# sc_v0.net
KiCad netlist of a schematic drawn in EAGLE
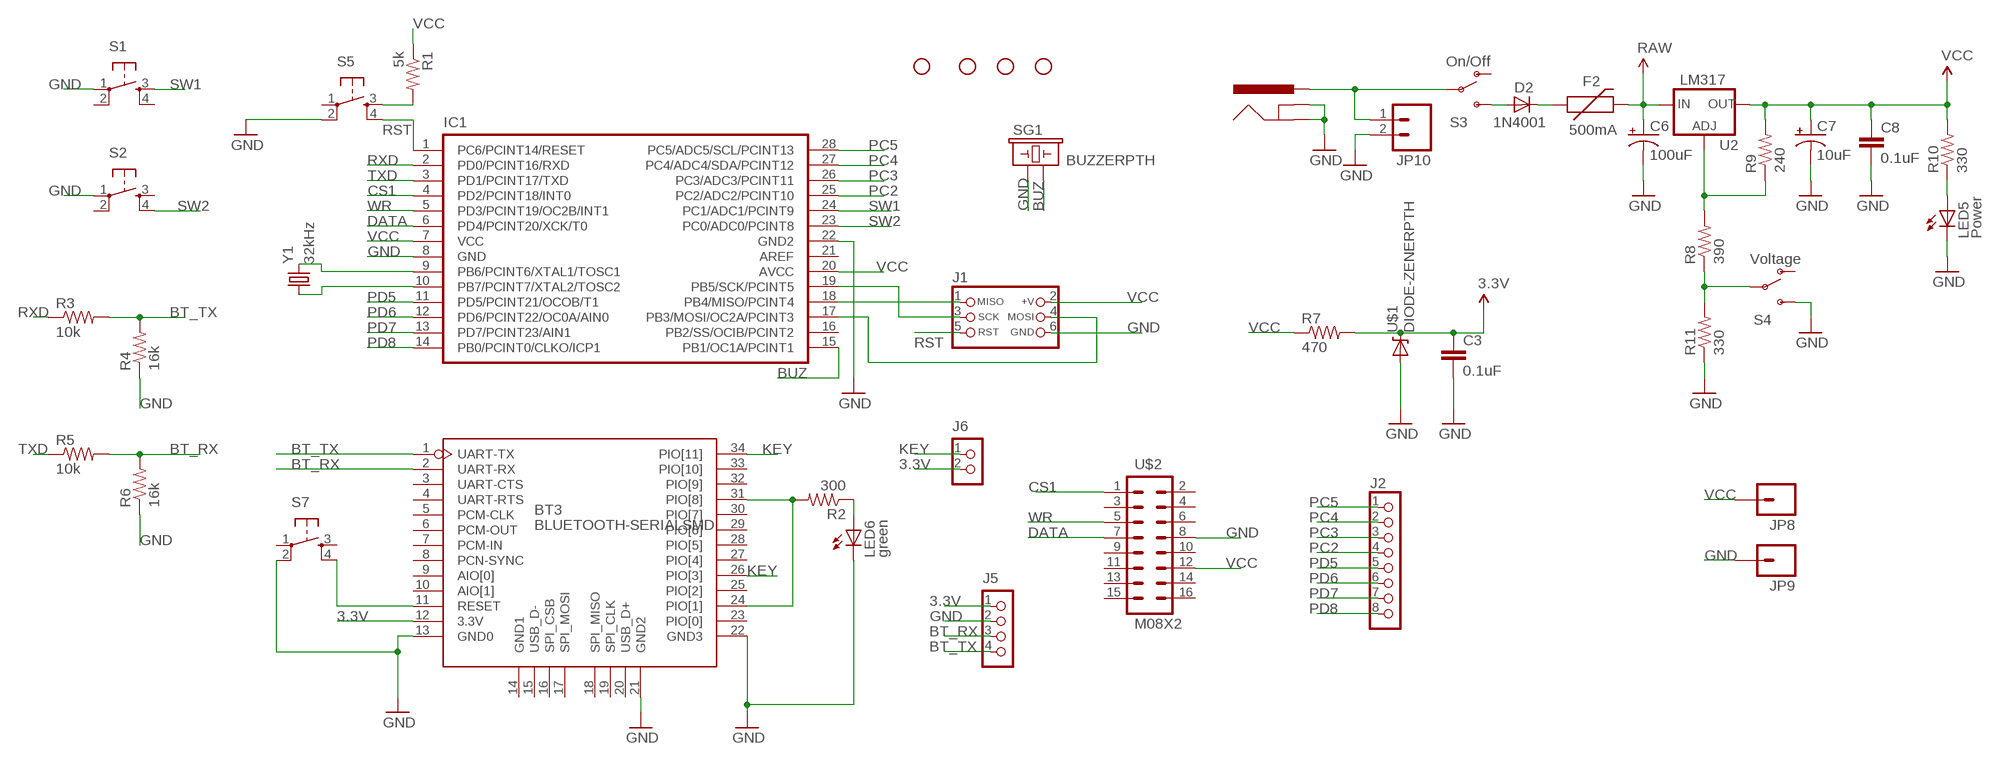
[diagram p0: schematic, sheet 1]

(export (version "E")
  (design (tool "Eeschema 10.0.6"))
  (components
    (comp (ref "BT3")
      (value "BLUETOOTH-SERIALSMD")
      (footprint "eagle-import:SERIAL_BLUETEETH")
      (libsource (lib "eagle-import") (part "BLUETOOTH-SERIALSMD"))
    )
    (comp (ref "C3")
      (value "0.1uF")
      (footprint "eagle-import:CAP-PTH-SMALL2")
      (libsource (lib "eagle-import") (part "CAPPTH2"))
    )
    (comp (ref "C6")
      (value "100uF")
      (footprint "eagle-import:CPOL-RADIAL-100UF-25V")
      (libsource (lib "eagle-import") (part "CAP_POLPTH1"))
    )
    (comp (ref "C7")
      (value "10uF")
      (footprint "eagle-import:CPOL-RADIAL-10UF-25V")
      (libsource (lib "eagle-import") (part "CAP_POLPTH2"))
    )
    (comp (ref "C8")
      (value "0.1uF")
      (footprint "eagle-import:CAP-PTH-SMALL2")
      (libsource (lib "eagle-import") (part "CAPPTH2"))
    )
    (comp (ref "D2")
      (value "1N4001")
      (footprint "eagle-import:DIODE-0.4")
      (libsource (lib "eagle-import") (part "DIODEPTH"))
    )
    (comp (ref "F2")
      (value "500mA")
      (footprint "eagle-import:PTC")
      (libsource (lib "eagle-import") (part "PTCPTH"))
    )
    (comp (ref "IC1")
      (value "IC_UC_ATMEGA328PDIL")
      (footprint "eagle-import:DIL28-N")
      (libsource (lib "eagle-import") (part "IC_UC_ATMEGA328PDIL"))
    )
    (comp (ref "J1")
      (value "CON_HEADER_PRG_AVR_ICSP")
      (footprint "eagle-import:HEADER_PRG_2X03")
      (libsource (lib "eagle-import") (part "CON_HEADER_PRG_AVR_ICSP"))
    )
    (comp (ref "J2")
      (value "CON_HEADER_1X08-PTH")
      (footprint "eagle-import:M1X8")
      (libsource (lib "eagle-import") (part "CON_HEADER_1X08-PTH"))
    )
    (comp (ref "J3")
      (value "POWER_JACKPTH")
      (footprint "eagle-import:POWER_JACK_PTH")
      (libsource (lib "eagle-import") (part "POWER_JACKPTH"))
    )
    (comp (ref "J5")
      (value "CON_HEADER_1X04")
      (footprint "eagle-import:M1X4")
      (libsource (lib "eagle-import") (part "CON_HEADER_1X04"))
    )
    (comp (ref "J6")
      (value "CON_HEADER_1X02-PTH")
      (footprint "eagle-import:M1X2")
      (libsource (lib "eagle-import") (part "CON_HEADER_1X02-PTH"))
    )
    (comp (ref "JP1")
      (value "STAND-OFF")
      (footprint "eagle-import:STAND-OFF")
      (libsource (lib "eagle-import") (part "STAND-OFF"))
    )
    (comp (ref "JP2")
      (value "STAND-OFF")
      (footprint "eagle-import:STAND-OFF")
      (libsource (lib "eagle-import") (part "STAND-OFF"))
    )
    (comp (ref "JP3")
      (value "STAND-OFF")
      (footprint "eagle-import:STAND-OFF")
      (libsource (lib "eagle-import") (part "STAND-OFF"))
    )
    (comp (ref "JP4")
      (value "STAND-OFF")
      (footprint "eagle-import:STAND-OFF")
      (libsource (lib "eagle-import") (part "STAND-OFF"))
    )
    (comp (ref "JP8")
      (value "M01PTH")
      (footprint "eagle-import:1X01")
      (libsource (lib "eagle-import") (part "M01PTH"))
    )
    (comp (ref "JP9")
      (value "M01PTH")
      (footprint "eagle-import:1X01")
      (libsource (lib "eagle-import") (part "M01PTH"))
    )
    (comp (ref "JP10")
      (value "M02PTH")
      (footprint "eagle-import:1X02")
      (libsource (lib "eagle-import") (part "M02PTH"))
    )
    (comp (ref "LED5")
      (value "Power")
      (footprint "eagle-import:LED5MM")
      (libsource (lib "eagle-import") (part "SparkFun-Nate_LED5MM"))
    )
    (comp (ref "LED6")
      (value "green")
      (footprint "eagle-import:LED3MM")
      (libsource (lib "eagle-import") (part "LED3MM"))
    )
    (comp (ref "R1")
      (value "5k")
      (footprint "eagle-import:AXIAL-0.3")
      (libsource (lib "eagle-import") (part "RESISTORAXIAL-0.3"))
    )
    (comp (ref "R2")
      (value "300")
      (footprint "eagle-import:AXIAL-0.3")
      (libsource (lib "eagle-import") (part "RESISTORAXIAL-0.3"))
    )
    (comp (ref "R3")
      (value "10k")
      (footprint "eagle-import:AXIAL-0.3")
      (libsource (lib "eagle-import") (part "RESISTORAXIAL-0.3"))
    )
    (comp (ref "R4")
      (value "16k")
      (footprint "eagle-import:AXIAL-0.3")
      (libsource (lib "eagle-import") (part "RESISTORAXIAL-0.3"))
    )
    (comp (ref "R5")
      (value "10k")
      (footprint "eagle-import:AXIAL-0.3")
      (libsource (lib "eagle-import") (part "RESISTORAXIAL-0.3"))
    )
    (comp (ref "R6")
      (value "16k")
      (footprint "eagle-import:AXIAL-0.3")
      (libsource (lib "eagle-import") (part "RESISTORAXIAL-0.3"))
    )
    (comp (ref "R7")
      (value "470")
      (footprint "eagle-import:AXIAL-0.3")
      (libsource (lib "eagle-import") (part "RESISTORAXIAL-0.3"))
    )
    (comp (ref "R8")
      (value "390")
      (footprint "eagle-import:AXIAL-0.3")
      (libsource (lib "eagle-import") (part "RESISTORAXIAL-0.3"))
    )
    (comp (ref "R9")
      (value "240")
      (footprint "eagle-import:AXIAL-0.3")
      (libsource (lib "eagle-import") (part "RESISTORAXIAL-0.3"))
    )
    (comp (ref "R10")
      (value "330")
      (footprint "eagle-import:AXIAL-0.3")
      (libsource (lib "eagle-import") (part "RESISTORAXIAL-0.3"))
    )
    (comp (ref "R11")
      (value "330")
      (footprint "eagle-import:AXIAL-0.3")
      (libsource (lib "eagle-import") (part "RESISTORAXIAL-0.3"))
    )
    (comp (ref "S1")
      (value "TAC_SWITCHPTH")
      (footprint "eagle-import:TACTILE-PTH")
      (libsource (lib "eagle-import") (part "TAC_SWITCHPTH"))
    )
    (comp (ref "S2")
      (value "TAC_SWITCHPTH")
      (footprint "eagle-import:TACTILE-PTH")
      (libsource (lib "eagle-import") (part "TAC_SWITCHPTH"))
    )
    (comp (ref "S3")
      (value "On/Off")
      (footprint "eagle-import:SWITCH-SPST")
      (libsource (lib "eagle-import") (part "SWITCH-SPSTPTH"))
    )
    (comp (ref "S4")
      (value "Voltage")
      (footprint "eagle-import:SWITCH-SPST")
      (libsource (lib "eagle-import") (part "SWITCH-SPSTPTH"))
    )
    (comp (ref "S5")
      (value "TAC_SWITCHPTH")
      (footprint "eagle-import:TACTILE-PTH")
      (libsource (lib "eagle-import") (part "TAC_SWITCHPTH"))
    )
    (comp (ref "S7")
      (value "TAC_SWITCHPTH")
      (footprint "eagle-import:TACTILE-PTH")
      (libsource (lib "eagle-import") (part "TAC_SWITCHPTH"))
    )
    (comp (ref "SG1")
      (value "BUZZERPTH")
      (footprint "eagle-import:BUZZER-12MM")
      (libsource (lib "eagle-import") (part "BUZZERPTH"))
    )
    (comp (ref "U$1")
      (value "DIODE-ZENERPTH")
      (footprint "eagle-import:DIODE-ZENER")
      (libsource (lib "eagle-import") (part "DIODE-ZENERPTH"))
    )
    (comp (ref "U$2")
      (value "M08X2")
      (footprint "eagle-import:2X8")
      (libsource (lib "eagle-import") (part "M08X2"))
    )
    (comp (ref "U2")
      (value "LM317")
      (footprint "eagle-import:TO220-ADJ")
      (libsource (lib "eagle-import") (part "V_REG_317SINK"))
    )
    (comp (ref "Y1")
      (value "32kHz")
      (footprint "eagle-import:TC38H")
      (libsource (lib "eagle-import") (part "CRYSTALTC38H"))
    )
  )
  (nets
    (net (code "1") (name "/BT_RX") (class "Default")
      (node (ref "BT3") (pin "2") (pinfunction "UART-RX_2") (pintype "bidirectional"))
      (node (ref "J5") (pin "3") (pinfunction "3_3") (pintype "bidirectional"))
      (node (ref "R5") (pin "P$2") (pinfunction "2_P$2") (pintype "passive"))
      (node (ref "R6") (pin "P$2") (pinfunction "2_P$2") (pintype "passive"))
    )
    (net (code "2") (name "/BT_TX") (class "Default")
      (node (ref "BT3") (pin "1") (pinfunction "UART-TX_1") (pintype "bidirectional"))
      (node (ref "J5") (pin "4") (pinfunction "4_4") (pintype "bidirectional"))
      (node (ref "R3") (pin "P$2") (pinfunction "2_P$2") (pintype "passive"))
      (node (ref "R4") (pin "P$2") (pinfunction "2_P$2") (pintype "passive"))
    )
    (net (code "3") (name "/BUZ") (class "Default")
      (node (ref "IC1") (pin "15") (pinfunction "PB1/OC1A/PCINT1_15") (pintype "bidirectional"))
      (node (ref "SG1") (pin "-") (pinfunction "2_-") (pintype "passive"))
    )
    (net (code "4") (name "/CS1") (class "Default")
      (node (ref "IC1") (pin "4") (pinfunction "PD2/PCINT18/INT0_4") (pintype "bidirectional"))
      (node (ref "U$2") (pin "1") (pinfunction "1_1") (pintype "passive"))
    )
    (net (code "5") (name "/DATA") (class "Default")
      (node (ref "IC1") (pin "6") (pinfunction "PD4/PCINT20/XCK/T0_6") (pintype "bidirectional"))
      (node (ref "U$2") (pin "7") (pinfunction "7_7") (pintype "passive"))
    )
    (net (code "6") (name "/KEY") (class "Default")
      (node (ref "BT3") (pin "26") (pinfunction "PIO[3]_26") (pintype "bidirectional"))
      (node (ref "BT3") (pin "34") (pinfunction "PIO[11]_34") (pintype "bidirectional"))
      (node (ref "J6") (pin "1") (pinfunction "1_1") (pintype "passive"))
    )
    (net (code "7") (name "/PC2") (class "Default")
      (node (ref "IC1") (pin "25") (pinfunction "PC2/ADC2/PCINT10_25") (pintype "bidirectional"))
      (node (ref "J2") (pin "4") (pinfunction "4_4") (pintype "passive"))
    )
    (net (code "8") (name "/PC3") (class "Default")
      (node (ref "IC1") (pin "26") (pinfunction "PC3/ADC3/PCINT11_26") (pintype "bidirectional"))
      (node (ref "J2") (pin "3") (pinfunction "3_3") (pintype "passive"))
    )
    (net (code "9") (name "/PC4") (class "Default")
      (node (ref "IC1") (pin "27") (pinfunction "PC4/ADC4/SDA/PCINT12_27") (pintype "bidirectional"))
      (node (ref "J2") (pin "2") (pinfunction "2_2") (pintype "passive"))
    )
    (net (code "10") (name "/PC5") (class "Default")
      (node (ref "IC1") (pin "28") (pinfunction "PC5/ADC5/SCL/PCINT13_28") (pintype "bidirectional"))
      (node (ref "J2") (pin "1") (pinfunction "1_1") (pintype "passive"))
    )
    (net (code "11") (name "/PD5") (class "Default")
      (node (ref "IC1") (pin "11") (pinfunction "PD5/PCINT21/OCOB/T1_11") (pintype "bidirectional"))
      (node (ref "J2") (pin "5") (pinfunction "5_5") (pintype "passive"))
    )
    (net (code "12") (name "/PD6") (class "Default")
      (node (ref "IC1") (pin "12") (pinfunction "PD6/PCINT22/OC0A/AIN0_12") (pintype "bidirectional"))
      (node (ref "J2") (pin "6") (pinfunction "6_6") (pintype "passive"))
    )
    (net (code "13") (name "/PD7") (class "Default")
      (node (ref "IC1") (pin "13") (pinfunction "PD7/PCINT23/AIN1_13") (pintype "bidirectional"))
      (node (ref "J2") (pin "7") (pinfunction "7_7") (pintype "passive"))
    )
    (net (code "14") (name "/PD8") (class "Default")
      (node (ref "IC1") (pin "14") (pinfunction "PB0/PCINT0/CLKO/ICP1_14") (pintype "bidirectional"))
      (node (ref "J2") (pin "8") (pinfunction "8_8") (pintype "passive"))
    )
    (net (code "15") (name "/RST") (class "Default")
      (node (ref "IC1") (pin "1") (pinfunction "PC6/PCINT14/RESET_1") (pintype "bidirectional"))
      (node (ref "J1") (pin "5") (pinfunction "RST_5") (pintype "passive"))
      (node (ref "S5") (pin "4") (pinfunction "4_4") (pintype "passive"))
    )
    (net (code "16") (name "/RXD") (class "Default")
      (node (ref "IC1") (pin "2") (pinfunction "PD0/PCINT16/RXD_2") (pintype "bidirectional"))
      (node (ref "R3") (pin "P$1") (pinfunction "1_P$1") (pintype "passive"))
    )
    (net (code "17") (name "/SW1") (class "Default")
      (node (ref "IC1") (pin "24") (pinfunction "PC1/ADC1/PCINT9_24") (pintype "bidirectional"))
      (node (ref "S1") (pin "3") (pinfunction "3_3") (pintype "passive"))
    )
    (net (code "18") (name "/SW2") (class "Default")
      (node (ref "IC1") (pin "23") (pinfunction "PC0/ADC0/PCINT8_23") (pintype "bidirectional"))
      (node (ref "S2") (pin "4") (pinfunction "4_4") (pintype "passive"))
    )
    (net (code "19") (name "/TXD") (class "Default")
      (node (ref "IC1") (pin "3") (pinfunction "PD1/PCINT17/TXD_3") (pintype "bidirectional"))
      (node (ref "R5") (pin "P$1") (pinfunction "1_P$1") (pintype "passive"))
    )
    (net (code "20") (name "/WR") (class "Default")
      (node (ref "IC1") (pin "5") (pinfunction "PD3/PCINT19/OC2B/INT1_5") (pintype "bidirectional"))
      (node (ref "U$2") (pin "5") (pinfunction "5_5") (pintype "passive"))
    )
    (net (code "21") (name "3.3V") (class "Default")
      (node (ref "BT3") (pin "12") (pinfunction "3.3V_12") (pintype "bidirectional"))
      (node (ref "C3") (pin "1") (pinfunction "1_1") (pintype "passive"))
      (node (ref "J5") (pin "1") (pinfunction "1_1") (pintype "bidirectional"))
      (node (ref "J6") (pin "2") (pinfunction "2_2") (pintype "passive"))
      (node (ref "R7") (pin "P$2") (pinfunction "2_P$2") (pintype "passive"))
      (node (ref "U$1") (pin "P$1") (pinfunction "C_P$1") (pintype "passive"))
    )
    (net (code "22") (name "GND") (class "Default")
      (node (ref "BT3") (pin "13") (pinfunction "GND0_13") (pintype "bidirectional"))
      (node (ref "BT3") (pin "21") (pinfunction "GND2_21") (pintype "bidirectional"))
      (node (ref "BT3") (pin "22") (pinfunction "GND3_22") (pintype "bidirectional"))
      (node (ref "C3") (pin "2") (pinfunction "2_2") (pintype "passive"))
      (node (ref "C6") (pin "2") (pinfunction "-_2") (pintype "passive"))
      (node (ref "C7") (pin "2") (pinfunction "-_2") (pintype "passive"))
      (node (ref "C8") (pin "2") (pinfunction "2_2") (pintype "passive"))
      (node (ref "IC1") (pin "22") (pinfunction "GND2_22") (pintype "bidirectional"))
      (node (ref "IC1") (pin "8") (pinfunction "GND_8") (pintype "bidirectional"))
      (node (ref "J1") (pin "6") (pinfunction "GND_6") (pintype "passive"))
      (node (ref "J3") (pin "GND") (pinfunction "GND_GND") (pintype "bidirectional"))
      (node (ref "J3") (pin "GNDBREAK") (pinfunction "GNDBREAK_GNDBREAK") (pintype "bidirectional"))
      (node (ref "J5") (pin "2") (pinfunction "2_2") (pintype "bidirectional"))
      (node (ref "JP10") (pin "2") (pinfunction "2_2") (pintype "passive"))
      (node (ref "JP9") (pin "1") (pinfunction "1_1") (pintype "passive"))
      (node (ref "LED5") (pin "K") (pinfunction "C_K") (pintype "passive"))
      (node (ref "LED6") (pin "K") (pinfunction "C_K") (pintype "passive"))
      (node (ref "R11") (pin "P$1") (pinfunction "1_P$1") (pintype "passive"))
      (node (ref "R4") (pin "P$1") (pinfunction "1_P$1") (pintype "passive"))
      (node (ref "R6") (pin "P$1") (pinfunction "1_P$1") (pintype "passive"))
      (node (ref "S1") (pin "1") (pinfunction "1_1") (pintype "passive"))
      (node (ref "S2") (pin "1") (pinfunction "1_1") (pintype "passive"))
      (node (ref "S4") (pin "3") (pinfunction "S_3") (pintype "passive"))
      (node (ref "S5") (pin "2") (pinfunction "2_2") (pintype "passive"))
      (node (ref "S7") (pin "2") (pinfunction "2_2") (pintype "passive"))
      (node (ref "SG1") (pin "+") (pinfunction "1_+") (pintype "passive"))
      (node (ref "U$1") (pin "P$2") (pinfunction "A_P$2") (pintype "passive"))
      (node (ref "U$2") (pin "8") (pinfunction "8_8") (pintype "passive"))
    )
    (net (code "23") (name "Net-(BT3-PIO[1])") (class "Default")
      (node (ref "BT3") (pin "24") (pinfunction "PIO[1]_24") (pintype "bidirectional"))
      (node (ref "BT3") (pin "31") (pinfunction "PIO[8]_31") (pintype "bidirectional"))
      (node (ref "R2") (pin "P$2") (pinfunction "2_P$2") (pintype "passive"))
    )
    (net (code "24") (name "Net-(BT3-RESET)") (class "Default")
      (node (ref "BT3") (pin "11") (pinfunction "RESET_11") (pintype "bidirectional"))
      (node (ref "S7") (pin "4") (pinfunction "4_4") (pintype "passive"))
    )
    (net (code "25") (name "Net-(F2-1)") (class "Default")
      (node (ref "D2") (pin "C") (pinfunction "C_C") (pintype "passive"))
      (node (ref "F2") (pin "P$1") (pinfunction "1_P$1") (pintype "bidirectional"))
    )
    (net (code "26") (name "Net-(IC1-PB3{slash}MOSI{slash}OC2A{slash}PCINT3)") (class "Default")
      (node (ref "IC1") (pin "17") (pinfunction "PB3/MOSI/OC2A/PCINT3_17") (pintype "bidirectional"))
      (node (ref "J1") (pin "4") (pinfunction "MOSI_4") (pintype "passive"))
    )
    (net (code "27") (name "Net-(IC1-PB4{slash}MISO{slash}PCINT4)") (class "Default")
      (node (ref "IC1") (pin "18") (pinfunction "PB4/MISO/PCINT4_18") (pintype "bidirectional"))
      (node (ref "J1") (pin "1") (pinfunction "MISO_1") (pintype "passive"))
    )
    (net (code "28") (name "Net-(IC1-PB5{slash}SCK{slash}PCINT5)") (class "Default")
      (node (ref "IC1") (pin "19") (pinfunction "PB5/SCK/PCINT5_19") (pintype "bidirectional"))
      (node (ref "J1") (pin "3") (pinfunction "SCK_3") (pintype "passive"))
    )
    (net (code "29") (name "Net-(IC1-PB6{slash}PCINT6{slash}XTAL1{slash}TOSC1)") (class "Default")
      (node (ref "IC1") (pin "9") (pinfunction "PB6/PCINT6/XTAL1/TOSC1_9") (pintype "bidirectional"))
      (node (ref "Y1") (pin "2") (pinfunction "2_2") (pintype "passive"))
    )
    (net (code "30") (name "Net-(IC1-PB7{slash}PCINT7{slash}XTAL2{slash}TOSC2)") (class "Default")
      (node (ref "IC1") (pin "10") (pinfunction "PB7/PCINT7/XTAL2/TOSC2_10") (pintype "bidirectional"))
      (node (ref "Y1") (pin "1") (pinfunction "1_1") (pintype "passive"))
    )
    (net (code "31") (name "Net-(R1-2)") (class "Default")
      (node (ref "R1") (pin "P$2") (pinfunction "2_P$2") (pintype "passive"))
      (node (ref "S5") (pin "3") (pinfunction "3_3") (pintype "passive"))
    )
    (net (code "32") (name "Net-(R2-1)") (class "Default")
      (node (ref "LED6") (pin "A") (pinfunction "A_A") (pintype "passive"))
      (node (ref "R2") (pin "P$1") (pinfunction "1_P$1") (pintype "passive"))
    )
    (net (code "33") (name "Net-(R8-2)") (class "Default")
      (node (ref "R8") (pin "P$2") (pinfunction "2_P$2") (pintype "passive"))
      (node (ref "R9") (pin "P$1") (pinfunction "1_P$1") (pintype "passive"))
      (node (ref "U2") (pin "ADJ") (pinfunction "ADJ_ADJ") (pintype "input"))
    )
    (net (code "34") (name "Net-(R10-1)") (class "Default")
      (node (ref "LED5") (pin "A") (pinfunction "A_A") (pintype "passive"))
      (node (ref "R10") (pin "P$1") (pinfunction "1_P$1") (pintype "passive"))
    )
    (net (code "35") (name "Net-(R11-2)") (class "Default")
      (node (ref "R11") (pin "P$2") (pinfunction "2_P$2") (pintype "passive"))
      (node (ref "R8") (pin "P$1") (pinfunction "1_P$1") (pintype "passive"))
      (node (ref "S4") (pin "2") (pinfunction "P_2") (pintype "passive"))
    )
    (net (code "36") (name "Net-(S3-P)") (class "Default")
      (node (ref "J3") (pin "PWR") (pinfunction "PWR_PWR") (pintype "bidirectional"))
      (node (ref "JP10") (pin "1") (pinfunction "1_1") (pintype "passive"))
      (node (ref "S3") (pin "2") (pinfunction "P_2") (pintype "passive"))
    )
    (net (code "37") (name "Net-(S3-S)") (class "Default")
      (node (ref "D2") (pin "A") (pinfunction "A_A") (pintype "passive"))
      (node (ref "S3") (pin "3") (pinfunction "S_3") (pintype "passive"))
    )
    (net (code "38") (name "RAW") (class "Default")
      (node (ref "C6") (pin "1") (pinfunction "+_1") (pintype "passive"))
      (node (ref "F2") (pin "P$2") (pinfunction "2_P$2") (pintype "bidirectional"))
      (node (ref "U2") (pin "IN") (pinfunction "IN_IN") (pintype "input"))
    )
    (net (code "39") (name "VCC") (class "Default")
      (node (ref "C7") (pin "1") (pinfunction "+_1") (pintype "passive"))
      (node (ref "C8") (pin "1") (pinfunction "1_1") (pintype "passive"))
      (node (ref "IC1") (pin "20") (pinfunction "AVCC_20") (pintype "bidirectional"))
      (node (ref "IC1") (pin "7") (pinfunction "VCC_7") (pintype "bidirectional"))
      (node (ref "J1") (pin "2") (pinfunction "+V_2") (pintype "passive"))
      (node (ref "JP8") (pin "1") (pinfunction "1_1") (pintype "passive"))
      (node (ref "R1") (pin "P$1") (pinfunction "1_P$1") (pintype "passive"))
      (node (ref "R10") (pin "P$2") (pinfunction "2_P$2") (pintype "passive"))
      (node (ref "R7") (pin "P$1") (pinfunction "1_P$1") (pintype "passive"))
      (node (ref "R9") (pin "P$2") (pinfunction "2_P$2") (pintype "passive"))
      (node (ref "U$2") (pin "12") (pinfunction "12_12") (pintype "passive"))
      (node (ref "U2") (pin "OUT") (pinfunction "OUT_OUT") (pintype "output"))
    )
    (net (code "40") (name "unconnected-(BT3-AIO[0]-Pad9)") (class "Default")
      (node (ref "BT3") (pin "9") (pinfunction "AIO[0]_9") (pintype "bidirectional"))
    )
    (net (code "41") (name "unconnected-(BT3-AIO[1]-Pad10)") (class "Default")
      (node (ref "BT3") (pin "10") (pinfunction "AIO[1]_10") (pintype "bidirectional"))
    )
    (net (code "42") (name "unconnected-(BT3-GND1-Pad14)") (class "Default")
      (node (ref "BT3") (pin "14") (pinfunction "GND1_14") (pintype "bidirectional"))
    )
    (net (code "43") (name "unconnected-(BT3-PCM-CLK-Pad5)") (class "Default")
      (node (ref "BT3") (pin "5") (pinfunction "PCM-CLK_5") (pintype "bidirectional"))
    )
    (net (code "44") (name "unconnected-(BT3-PCM-IN-Pad7)") (class "Default")
      (node (ref "BT3") (pin "7") (pinfunction "PCM-IN_7") (pintype "bidirectional"))
    )
    (net (code "45") (name "unconnected-(BT3-PCM-OUT-Pad6)") (class "Default")
      (node (ref "BT3") (pin "6") (pinfunction "PCM-OUT_6") (pintype "bidirectional"))
    )
    (net (code "46") (name "unconnected-(BT3-PCN-SYNC-Pad8)") (class "Default")
      (node (ref "BT3") (pin "8") (pinfunction "PCN-SYNC_8") (pintype "bidirectional"))
    )
    (net (code "47") (name "unconnected-(BT3-PIO[0]-Pad23)") (class "Default")
      (node (ref "BT3") (pin "23") (pinfunction "PIO[0]_23") (pintype "bidirectional"))
    )
    (net (code "48") (name "unconnected-(BT3-PIO[2]-Pad25)") (class "Default")
      (node (ref "BT3") (pin "25") (pinfunction "PIO[2]_25") (pintype "bidirectional"))
    )
    (net (code "49") (name "unconnected-(BT3-PIO[4]-Pad27)") (class "Default")
      (node (ref "BT3") (pin "27") (pinfunction "PIO[4]_27") (pintype "bidirectional"))
    )
    (net (code "50") (name "unconnected-(BT3-PIO[5]-Pad28)") (class "Default")
      (node (ref "BT3") (pin "28") (pinfunction "PIO[5]_28") (pintype "bidirectional"))
    )
    (net (code "51") (name "unconnected-(BT3-PIO[6]-Pad29)") (class "Default")
      (node (ref "BT3") (pin "29") (pinfunction "PIO[6]_29") (pintype "bidirectional"))
    )
    (net (code "52") (name "unconnected-(BT3-PIO[7]-Pad30)") (class "Default")
      (node (ref "BT3") (pin "30") (pinfunction "PIO[7]_30") (pintype "bidirectional"))
    )
    (net (code "53") (name "unconnected-(BT3-PIO[9]-Pad32)") (class "Default")
      (node (ref "BT3") (pin "32") (pinfunction "PIO[9]_32") (pintype "bidirectional"))
    )
    (net (code "54") (name "unconnected-(BT3-PIO[10]-Pad33)") (class "Default")
      (node (ref "BT3") (pin "33") (pinfunction "PIO[10]_33") (pintype "bidirectional"))
    )
    (net (code "55") (name "unconnected-(BT3-SPI_CLK-Pad19)") (class "Default")
      (node (ref "BT3") (pin "19") (pinfunction "SPI_CLK_19") (pintype "bidirectional"))
    )
    (net (code "56") (name "unconnected-(BT3-SPI_CSB-Pad16)") (class "Default")
      (node (ref "BT3") (pin "16") (pinfunction "SPI_CSB_16") (pintype "bidirectional"))
    )
    (net (code "57") (name "unconnected-(BT3-SPI_MISO-Pad18)") (class "Default")
      (node (ref "BT3") (pin "18") (pinfunction "SPI_MISO_18") (pintype "bidirectional"))
    )
    (net (code "58") (name "unconnected-(BT3-SPI_MOSI-Pad17)") (class "Default")
      (node (ref "BT3") (pin "17") (pinfunction "SPI_MOSI_17") (pintype "bidirectional"))
    )
    (net (code "59") (name "unconnected-(BT3-UART-CTS-Pad3)") (class "Default")
      (node (ref "BT3") (pin "3") (pinfunction "UART-CTS_3") (pintype "bidirectional"))
    )
    (net (code "60") (name "unconnected-(BT3-UART-RTS-Pad4)") (class "Default")
      (node (ref "BT3") (pin "4") (pinfunction "UART-RTS_4") (pintype "bidirectional"))
    )
    (net (code "61") (name "unconnected-(BT3-USB_D+-Pad20)") (class "Default")
      (node (ref "BT3") (pin "20") (pinfunction "USB_D+_20") (pintype "bidirectional"))
    )
    (net (code "62") (name "unconnected-(BT3-USB_D--Pad15)") (class "Default")
      (node (ref "BT3") (pin "15") (pinfunction "USB_D-_15") (pintype "bidirectional"))
    )
    (net (code "63") (name "unconnected-(IC1-AREF-Pad21)") (class "Default")
      (node (ref "IC1") (pin "21") (pinfunction "AREF_21") (pintype "bidirectional"))
    )
    (net (code "64") (name "unconnected-(IC1-PB2{slash}SS{slash}OCIB{slash}PCINT2-Pad16)") (class "Default")
      (node (ref "IC1") (pin "16") (pinfunction "PB2/SS/OCIB/PCINT2_16") (pintype "bidirectional"))
    )
    (net (code "65") (name "unconnected-(S1-Pad2)") (class "Default")
      (node (ref "S1") (pin "2") (pinfunction "2_2") (pintype "passive"))
    )
    (net (code "66") (name "unconnected-(S1-Pad4)") (class "Default")
      (node (ref "S1") (pin "4") (pinfunction "4_4") (pintype "passive"))
    )
    (net (code "67") (name "unconnected-(S2-Pad2)") (class "Default")
      (node (ref "S2") (pin "2") (pinfunction "2_2") (pintype "passive"))
    )
    (net (code "68") (name "unconnected-(S2-Pad3)") (class "Default")
      (node (ref "S2") (pin "3") (pinfunction "3_3") (pintype "passive"))
    )
    (net (code "69") (name "unconnected-(S3-O-Pad1)") (class "Default")
      (node (ref "S3") (pin "1") (pinfunction "O_1") (pintype "passive"))
    )
    (net (code "70") (name "unconnected-(S4-O-Pad1)") (class "Default")
      (node (ref "S4") (pin "1") (pinfunction "O_1") (pintype "passive"))
    )
    (net (code "71") (name "unconnected-(S5-Pad1)") (class "Default")
      (node (ref "S5") (pin "1") (pinfunction "1_1") (pintype "passive"))
    )
    (net (code "72") (name "unconnected-(S7-Pad1)") (class "Default")
      (node (ref "S7") (pin "1") (pinfunction "1_1") (pintype "passive"))
    )
    (net (code "73") (name "unconnected-(S7-Pad3)") (class "Default")
      (node (ref "S7") (pin "3") (pinfunction "3_3") (pintype "passive"))
    )
    (net (code "74") (name "unconnected-(U$2-Pad2)") (class "Default")
      (node (ref "U$2") (pin "2") (pinfunction "2_2") (pintype "passive"))
    )
    (net (code "75") (name "unconnected-(U$2-Pad3)") (class "Default")
      (node (ref "U$2") (pin "3") (pinfunction "3_3") (pintype "passive"))
    )
    (net (code "76") (name "unconnected-(U$2-Pad4)") (class "Default")
      (node (ref "U$2") (pin "4") (pinfunction "4_4") (pintype "passive"))
    )
    (net (code "77") (name "unconnected-(U$2-Pad6)") (class "Default")
      (node (ref "U$2") (pin "6") (pinfunction "6_6") (pintype "passive"))
    )
    (net (code "78") (name "unconnected-(U$2-Pad9)") (class "Default")
      (node (ref "U$2") (pin "9") (pinfunction "9_9") (pintype "passive"))
    )
    (net (code "79") (name "unconnected-(U$2-Pad10)") (class "Default")
      (node (ref "U$2") (pin "10") (pinfunction "10_10") (pintype "passive"))
    )
    (net (code "80") (name "unconnected-(U$2-Pad11)") (class "Default")
      (node (ref "U$2") (pin "11") (pinfunction "11_11") (pintype "passive"))
    )
    (net (code "81") (name "unconnected-(U$2-Pad13)") (class "Default")
      (node (ref "U$2") (pin "13") (pinfunction "13_13") (pintype "passive"))
    )
    (net (code "82") (name "unconnected-(U$2-Pad14)") (class "Default")
      (node (ref "U$2") (pin "14") (pinfunction "14_14") (pintype "passive"))
    )
    (net (code "83") (name "unconnected-(U$2-Pad15)") (class "Default")
      (node (ref "U$2") (pin "15") (pinfunction "15_15") (pintype "passive"))
    )
    (net (code "84") (name "unconnected-(U$2-Pad16)") (class "Default")
      (node (ref "U$2") (pin "16") (pinfunction "16_16") (pintype "passive"))
    )
  )
)
